# Lan.net
KiCad netlist of a schematic drawn in Altium Designer
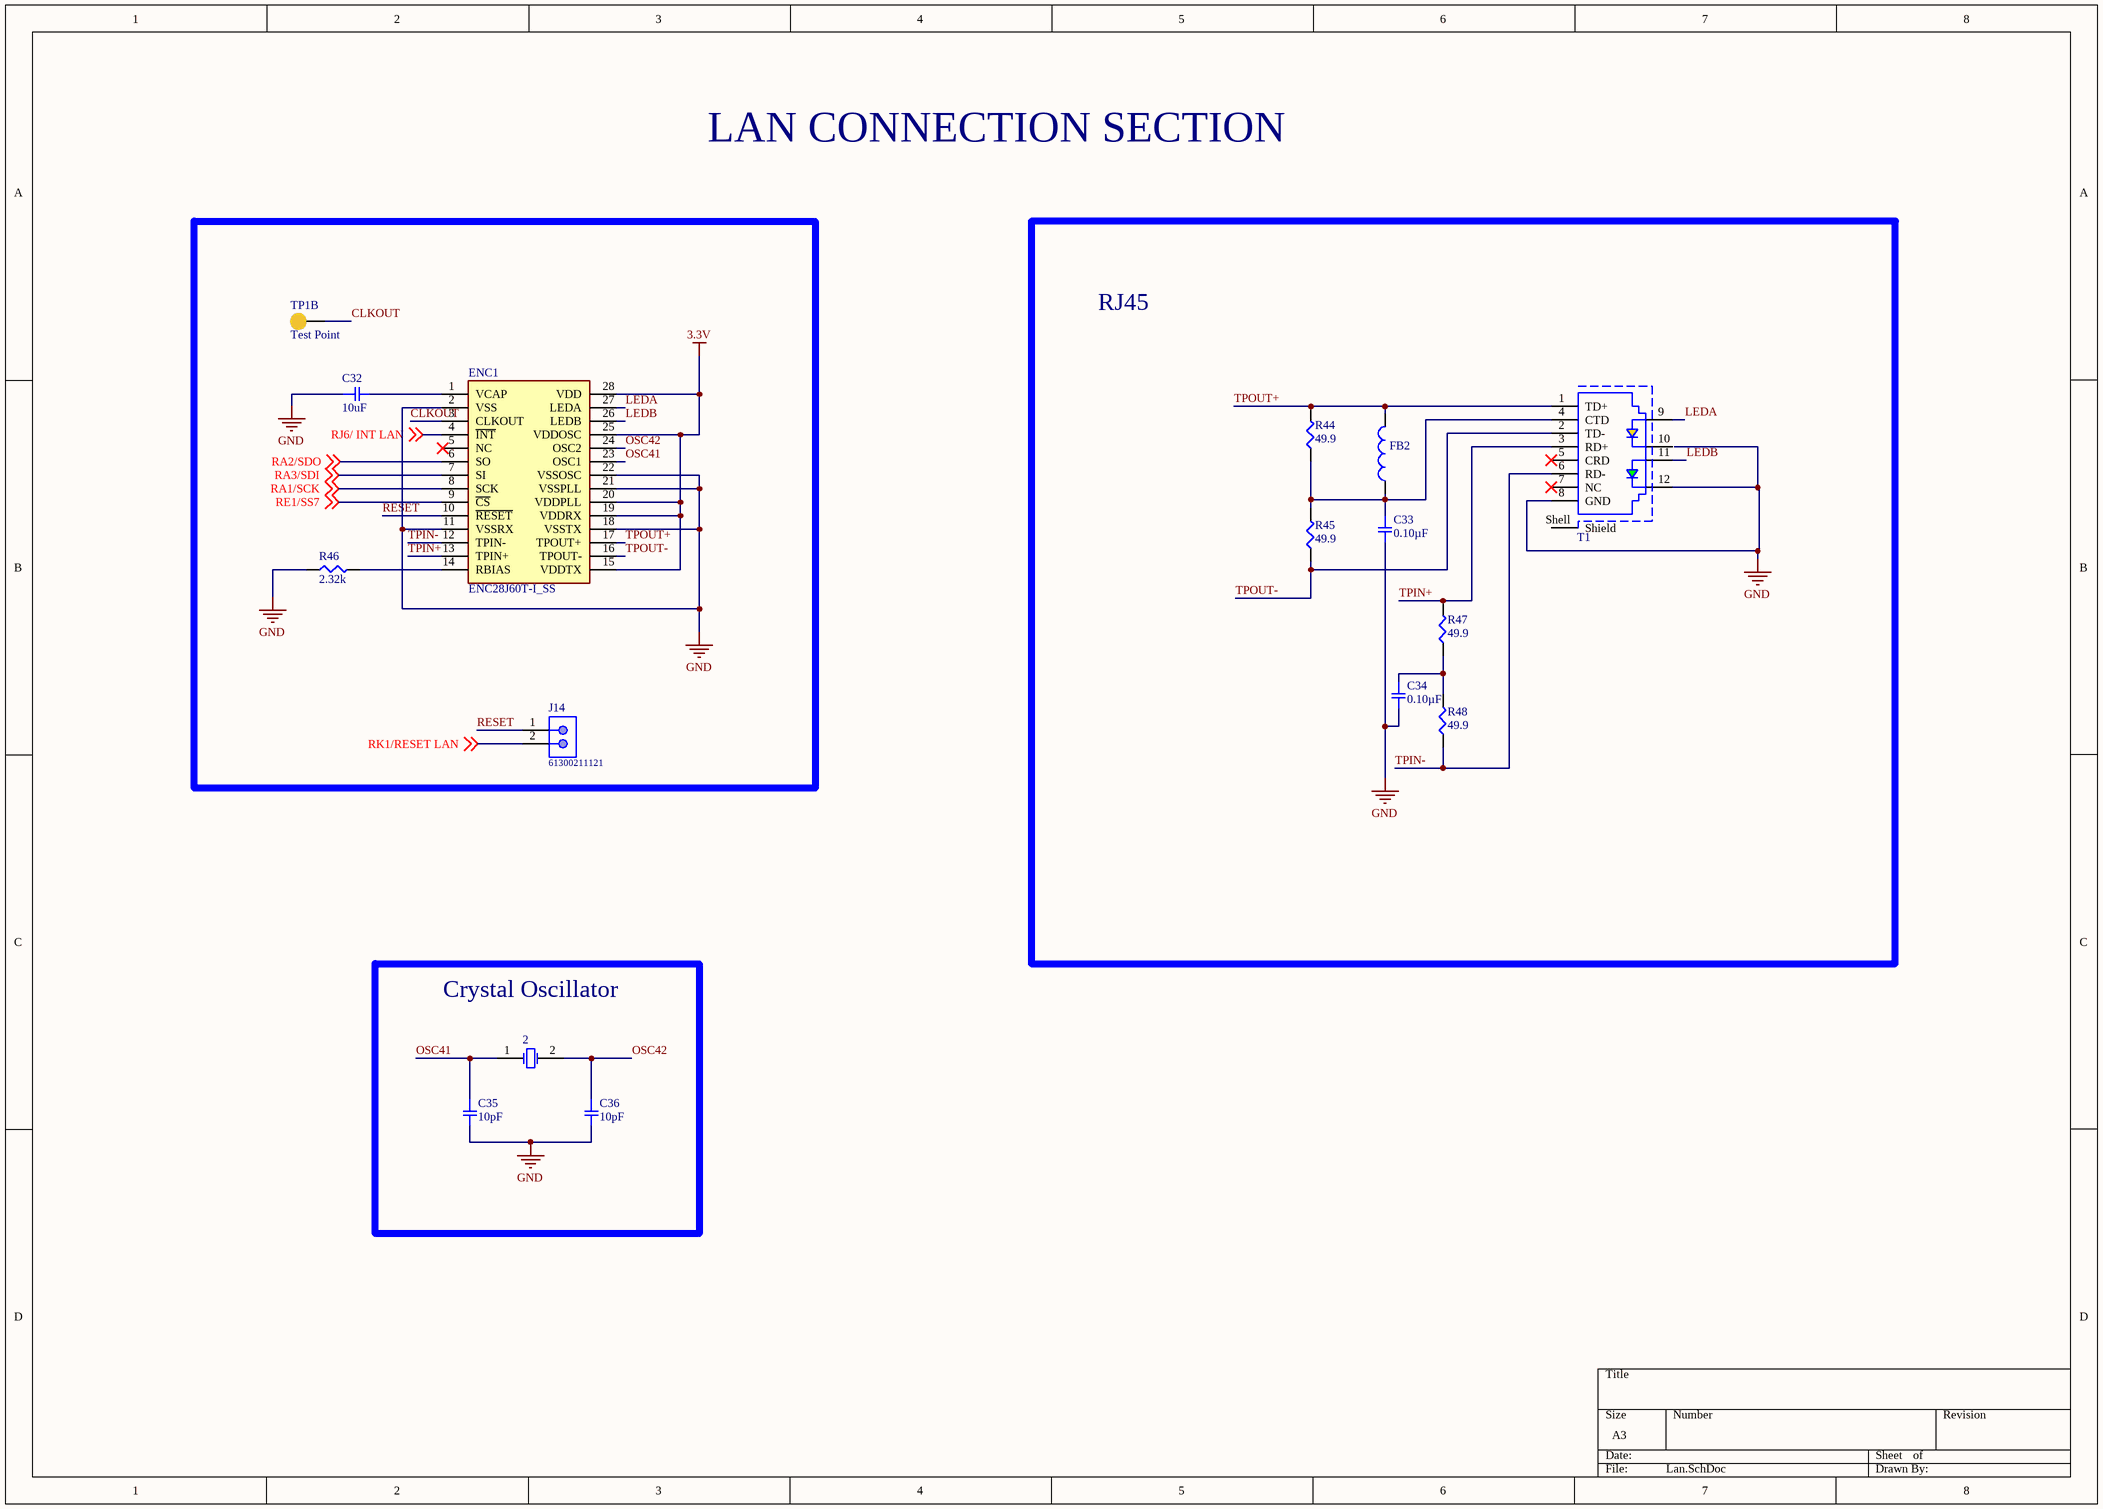
[diagram p0: Lan.SchDoc]

(export (version "E")
  (design (tool "Eeschema 10.0.6"))
  (components
    (comp (ref "2")
      (value "~")
      (footprint "Mini Crystal")
      (description "9B-64.000MBBK-B")
      (fields (field (name "MANUFACTURER") "Abracon") (field (name "PARTNUMBER") "ABLS2-4.096MHZ-D4Y-T"))
      (libsource (lib "Medi Custom library") (part "Mini Crystal"))
    )
    (comp (ref "C32")
      (value "10uF")
      (footprint "SMD-0805C")
      (description "CAP CER 0.1UF 50V X7R 0805")
      (fields
        (field (name "DIGI-KEY PART NUMBER") "490-11955-1-ND")
        (field (name "PART NUMBER") "GCD21BR71H104KA01L")
      )
      (libsource (lib "capacitor_murata_0805") (part "GCD21BR71H104KA01L"))
    )
    (comp (ref "C33")
      (value "0.10µF")
      (footprint "SMD-0805C")
      (description "CAP CER 0.1UF 50V X7R 0805")
      (fields
        (field (name "DIGI-KEY PART NUMBER") "490-11955-1-ND")
        (field (name "PART NUMBER") "GCD21BR71H104KA01L")
      )
      (libsource (lib "capacitor_murata_0805") (part "GCD21BR71H104KA01L"))
    )
    (comp (ref "C34")
      (value "0.10µF")
      (footprint "SMD-0805C")
      (description "CAP CER 0.1UF 50V X7R 0805")
      (fields
        (field (name "DIGI-KEY PART NUMBER") "490-11955-1-ND")
        (field (name "PART NUMBER") "GCD21BR71H104KA01L")
      )
      (libsource (lib "capacitor_murata_0805") (part "GCD21BR71H104KA01L"))
    )
    (comp (ref "C35")
      (value "10pF")
      (footprint "SMD-0805C")
      (description "CAP CER 0.1UF 50V X7R 0805")
      (fields
        (field (name "DIGI-KEY PART NUMBER") "490-11955-1-ND")
        (field (name "PART NUMBER") "GCD21BR71H104KA01L")
      )
      (libsource (lib "capacitor_murata_0805") (part "GCD21BR71H104KA01L"))
    )
    (comp (ref "C36")
      (value "10pF")
      (footprint "SMD-0805C")
      (description "CAP CER 0.1UF 50V X7R 0805")
      (fields
        (field (name "DIGI-KEY PART NUMBER") "490-11955-1-ND")
        (field (name "PART NUMBER") "GCD21BR71H104KA01L")
      )
      (libsource (lib "capacitor_murata_0805") (part "GCD21BR71H104KA01L"))
    )
    (comp (ref "ENC1")
      (value "ENC28J60T-I_SS")
      (footprint "SamacSys:SOP65P780X200-28N")
      (description "Integrated Circuit")
      (fields
        (field (name "MANUFACTURER_PART_NUMBER") "ENC28J60T-I/SS")
        (field (name "MOUSER PART NUMBER") "579-ENC28J60T-I/SS")
      )
      (libsource (lib "*") (part "ENC28J60T-I_SS"))
    )
    (comp (ref "FB2")
      (value "320Ohm")
      (footprint "WE-MPSA_0805_L2W1.2H0.9")
      (description "WE-MPSA EMI Multilayer Power Suppresion Bead, size 0805, 320Ohm, 2.5A")
      (fields
        (field (name "MANUFACTURER PART NUMBER") "78279220321")
        (field (name "MANUFACTURER") "Wurth Elektronik")
      )
      (libsource (lib "FB WURTH 2") (part "78279220321"))
    )
    (comp (ref "J14")
      (value "61300211121")
      (footprint "61300211121")
      (description "WR-PHD Pin Header, THT, pitch 2.54mm, Single Row, Vertical, 2pin")
      (fields (field (name "PUBLISHER") "Wurth Elektronik"))
      (libsource (lib "SIL_Connectors WR-PHD_rev19a") (part "61300211121"))
    )
    (comp (ref "R44")
      (value "49.9")
      (footprint "SMD-0805-RES")
      (description "RES SMD 49.9 OHM 1% 1/8W 0805")
      (fields
        (field (name "PART NUMBER") "ERJ-6ENF49R9V")
        (field (name "DIGI-KEY PART NUMBER") "P49.9CCT-ND")
      )
      (libsource (lib "Panasonic_ERJ_0805") (part "ERJ-6ENF49R9V"))
    )
    (comp (ref "R45")
      (value "49.9")
      (footprint "SMD-0805-RES")
      (description "RES SMD 49.9 OHM 1% 1/8W 0805")
      (fields
        (field (name "PART NUMBER") "ERJ-6ENF49R9V")
        (field (name "DIGI-KEY PART NUMBER") "P49.9CCT-ND")
      )
      (libsource (lib "Panasonic_ERJ_0805") (part "ERJ-6ENF49R9V"))
    )
    (comp (ref "R46")
      (value "2.32k")
      (footprint "SMD-0805-RES")
      (description "RES SMD 2.32K OHM 1% 1/8W 0805")
      (fields
        (field (name "PART NUMBER") "ERJ-6ENF2321V")
        (field (name "DIGI-KEY PART NUMBER") "P2.32KCCT-ND")
      )
      (libsource (lib "Panasonic_ERJ_0805") (part "ERJ-6ENF2321V"))
    )
    (comp (ref "R47")
      (value "49.9")
      (footprint "SMD-0805-RES")
      (description "RES SMD 49.9 OHM 1% 1/8W 0805")
      (fields
        (field (name "PART NUMBER") "ERJ-6ENF49R9V")
        (field (name "DIGI-KEY PART NUMBER") "P49.9CCT-ND")
      )
      (libsource (lib "Panasonic_ERJ_0805") (part "ERJ-6ENF49R9V"))
    )
    (comp (ref "R48")
      (value "49.9")
      (footprint "SMD-0805-RES")
      (description "RES SMD 49.9 OHM 1% 1/8W 0805")
      (fields
        (field (name "PART NUMBER") "ERJ-6ENF49R9V")
        (field (name "DIGI-KEY PART NUMBER") "P49.9CCT-ND")
      )
      (libsource (lib "Panasonic_ERJ_0805") (part "ERJ-6ENF49R9V"))
    )
    (comp (ref "T1")
      (value "ARJM11D7-009-AB-EW2")
      (footprint "74990111211")
      (description "WE-RJ45 LAN Transformer, THT, 1 Port, 10/100 Base-T, Tab Down")
      (fields
        (field (name "MANUFACTURER PART NUMBER") "74990111211")
        (field (name "MANUFACTURER") "Wurth Elektronik")
      )
      (libsource (lib "wurth rj45  3") (part "74990111211"))
    )
    (comp (ref "TP1")
      (value "Test Point")
      (footprint "pad2")
      (description "Top Testpoint Pad")
      (libsource (lib "Schlib1") (part "pad2"))
    )
  )
  (nets
    (net (code "1") (name "/CLKOUT") (class "Default")
      (node (ref "ENC1") (pin "3") (pinfunction "CLKOUT_3") (pintype "passive"))
      (node (ref "TP1") (pin "1") (pinfunction "1_1") (pintype "passive"))
    )
    (net (code "2") (name "/LEDA") (class "Default")
      (node (ref "ENC1") (pin "27") (pinfunction "LEDA_27") (pintype "passive"))
      (node (ref "T1") (pin "9") (pinfunction "9_9") (pintype "passive"))
    )
    (net (code "3") (name "/LEDB") (class "Default")
      (node (ref "ENC1") (pin "26") (pinfunction "LEDB_26") (pintype "passive"))
      (node (ref "T1") (pin "11") (pinfunction "11_11") (pintype "passive"))
    )
    (net (code "4") (name "/OSC41") (class "Default")
      (node (ref "2") (pin "1") (pinfunction "X1_1") (pintype "passive"))
      (node (ref "C35") (pin "1") (pinfunction "1_1") (pintype "passive"))
      (node (ref "ENC1") (pin "23") (pinfunction "OSC1_23") (pintype "passive"))
    )
    (net (code "5") (name "/OSC42") (class "Default")
      (node (ref "2") (pin "2") (pinfunction "X2_2") (pintype "passive"))
      (node (ref "C36") (pin "1") (pinfunction "1_1") (pintype "passive"))
      (node (ref "ENC1") (pin "24") (pinfunction "OSC2_24") (pintype "passive"))
    )
    (net (code "6") (name "/RESET") (class "Default")
      (node (ref "ENC1") (pin "10") (pinfunction "~{RESET}_10") (pintype "passive"))
      (node (ref "J14") (pin "1") (pinfunction "1_1") (pintype "passive"))
    )
    (net (code "7") (name "/TPIN+") (class "Default")
      (node (ref "ENC1") (pin "13") (pinfunction "TPIN+_13") (pintype "passive"))
      (node (ref "R47") (pin "2") (pinfunction "2_2") (pintype "passive"))
      (node (ref "T1") (pin "3") (pinfunction "RD+_3") (pintype "passive"))
    )
    (net (code "8") (name "/TPIN-") (class "Default")
      (node (ref "ENC1") (pin "12") (pinfunction "TPIN-_12") (pintype "passive"))
      (node (ref "R48") (pin "1") (pinfunction "1_1") (pintype "passive"))
      (node (ref "T1") (pin "6") (pinfunction "RD-_6") (pintype "passive"))
    )
    (net (code "9") (name "/TPOUT+") (class "Default")
      (node (ref "ENC1") (pin "17") (pinfunction "TPOUT+_17") (pintype "passive"))
      (node (ref "FB2") (pin "2") (pinfunction "2_2") (pintype "passive"))
      (node (ref "R44") (pin "2") (pinfunction "2_2") (pintype "passive"))
      (node (ref "T1") (pin "1") (pinfunction "TD+_1") (pintype "passive"))
    )
    (net (code "10") (name "/TPOUT-") (class "Default")
      (node (ref "ENC1") (pin "16") (pinfunction "TPOUT-_16") (pintype "passive"))
      (node (ref "R45") (pin "1") (pinfunction "1_1") (pintype "passive"))
      (node (ref "T1") (pin "2") (pinfunction "TD-_2") (pintype "passive"))
    )
    (net (code "11") (name "3.3V") (class "Default")
      (node (ref "ENC1") (pin "15") (pinfunction "VDDTX_15") (pintype "passive"))
      (node (ref "ENC1") (pin "19") (pinfunction "VDDRX_19") (pintype "passive"))
      (node (ref "ENC1") (pin "20") (pinfunction "VDDPLL_20") (pintype "passive"))
      (node (ref "ENC1") (pin "25") (pinfunction "VDDOSC_25") (pintype "passive"))
      (node (ref "ENC1") (pin "28") (pinfunction "VDD_28") (pintype "passive"))
    )
    (net (code "12") (name "GND") (class "Default")
      (node (ref "C32") (pin "1") (pinfunction "1_1") (pintype "passive"))
      (node (ref "C33") (pin "2") (pinfunction "2_2") (pintype "passive"))
      (node (ref "C34") (pin "2") (pinfunction "2_2") (pintype "passive"))
      (node (ref "C35") (pin "2") (pinfunction "2_2") (pintype "passive"))
      (node (ref "C36") (pin "2") (pinfunction "2_2") (pintype "passive"))
      (node (ref "ENC1") (pin "11") (pinfunction "VSSRX_11") (pintype "passive"))
      (node (ref "ENC1") (pin "18") (pinfunction "VSSTX_18") (pintype "passive"))
      (node (ref "ENC1") (pin "2") (pinfunction "VSS_2") (pintype "passive"))
      (node (ref "ENC1") (pin "21") (pinfunction "VSSPLL_21") (pintype "passive"))
      (node (ref "ENC1") (pin "22") (pinfunction "VSSOSC_22") (pintype "passive"))
      (node (ref "R46") (pin "1") (pinfunction "1_1") (pintype "passive"))
      (node (ref "T1") (pin "12") (pinfunction "12_12") (pintype "passive"))
      (node (ref "T1") (pin "8") (pinfunction "GND_8") (pintype "passive"))
    )
    (net (code "13") (name "Net-(C34-Pad1)") (class "Default")
      (node (ref "C34") (pin "1") (pinfunction "1_1") (pintype "passive"))
      (node (ref "R47") (pin "1") (pinfunction "1_1") (pintype "passive"))
      (node (ref "R48") (pin "2") (pinfunction "2_2") (pintype "passive"))
    )
    (net (code "14") (name "Net-(ENC1-RBIAS)") (class "Default")
      (node (ref "ENC1") (pin "14") (pinfunction "RBIAS_14") (pintype "passive"))
      (node (ref "R46") (pin "2") (pinfunction "2_2") (pintype "passive"))
    )
    (net (code "15") (name "Net-(ENC1-VCAP)") (class "Default")
      (node (ref "C32") (pin "2") (pinfunction "2_2") (pintype "passive"))
      (node (ref "ENC1") (pin "1") (pinfunction "VCAP_1") (pintype "passive"))
    )
    (net (code "16") (name "Net-(T1-CTD)") (class "Default")
      (node (ref "C33") (pin "1") (pinfunction "1_1") (pintype "passive"))
      (node (ref "FB2") (pin "1") (pinfunction "1_1") (pintype "passive"))
      (node (ref "R44") (pin "1") (pinfunction "1_1") (pintype "passive"))
      (node (ref "R45") (pin "2") (pinfunction "2_2") (pintype "passive"))
      (node (ref "T1") (pin "4") (pinfunction "CTD_4") (pintype "passive"))
    )
    (net (code "17") (name "RA1{slash}SCK") (class "Default")
      (node (ref "ENC1") (pin "8") (pinfunction "SCK_8") (pintype "passive"))
    )
    (net (code "18") (name "RA2{slash}SDO") (class "Default")
      (node (ref "ENC1") (pin "6") (pinfunction "SO_6") (pintype "passive"))
    )
    (net (code "19") (name "RA3{slash}SDI") (class "Default")
      (node (ref "ENC1") (pin "7") (pinfunction "SI_7") (pintype "passive"))
    )
    (net (code "20") (name "RE1{slash}SS7") (class "Default")
      (node (ref "ENC1") (pin "9") (pinfunction "~{CS}_9") (pintype "passive"))
    )
    (net (code "21") (name "RJ6{slash} INT LAN") (class "Default")
      (node (ref "ENC1") (pin "4") (pinfunction "~{INT}_4") (pintype "passive"))
    )
    (net (code "22") (name "RK1{slash}RESET LAN") (class "Default")
      (node (ref "J14") (pin "2") (pinfunction "2_2") (pintype "passive"))
    )
    (net (code "23") (name "unconnected-(ENC1-NC-Pad5)") (class "Default")
      (node (ref "ENC1") (pin "5") (pinfunction "NC_5") (pintype "passive"))
    )
    (net (code "24") (name "unconnected-(T1-CRD-Pad5)") (class "Default")
      (node (ref "T1") (pin "5") (pinfunction "CRD_5") (pintype "passive+no_connect"))
    )
    (net (code "25") (name "unconnected-(T1-NC-Pad7)") (class "Default")
      (node (ref "T1") (pin "7") (pinfunction "NC_7") (pintype "passive+no_connect"))
    )
    (net (code "26") (name "unconnected-(T1-Pad10)") (class "Default")
      (node (ref "T1") (pin "10") (pinfunction "10_10") (pintype "passive"))
    )
    (net (code "27") (name "unconnected-(T1-Shield-PadShell)") (class "Default")
      (node (ref "T1") (pin "Shell") (pinfunction "Shield_Shell") (pintype "passive"))
    )
  )
)
